# solo-fp1020.net
KiCad netlist of a schematic drawn in EAGLE
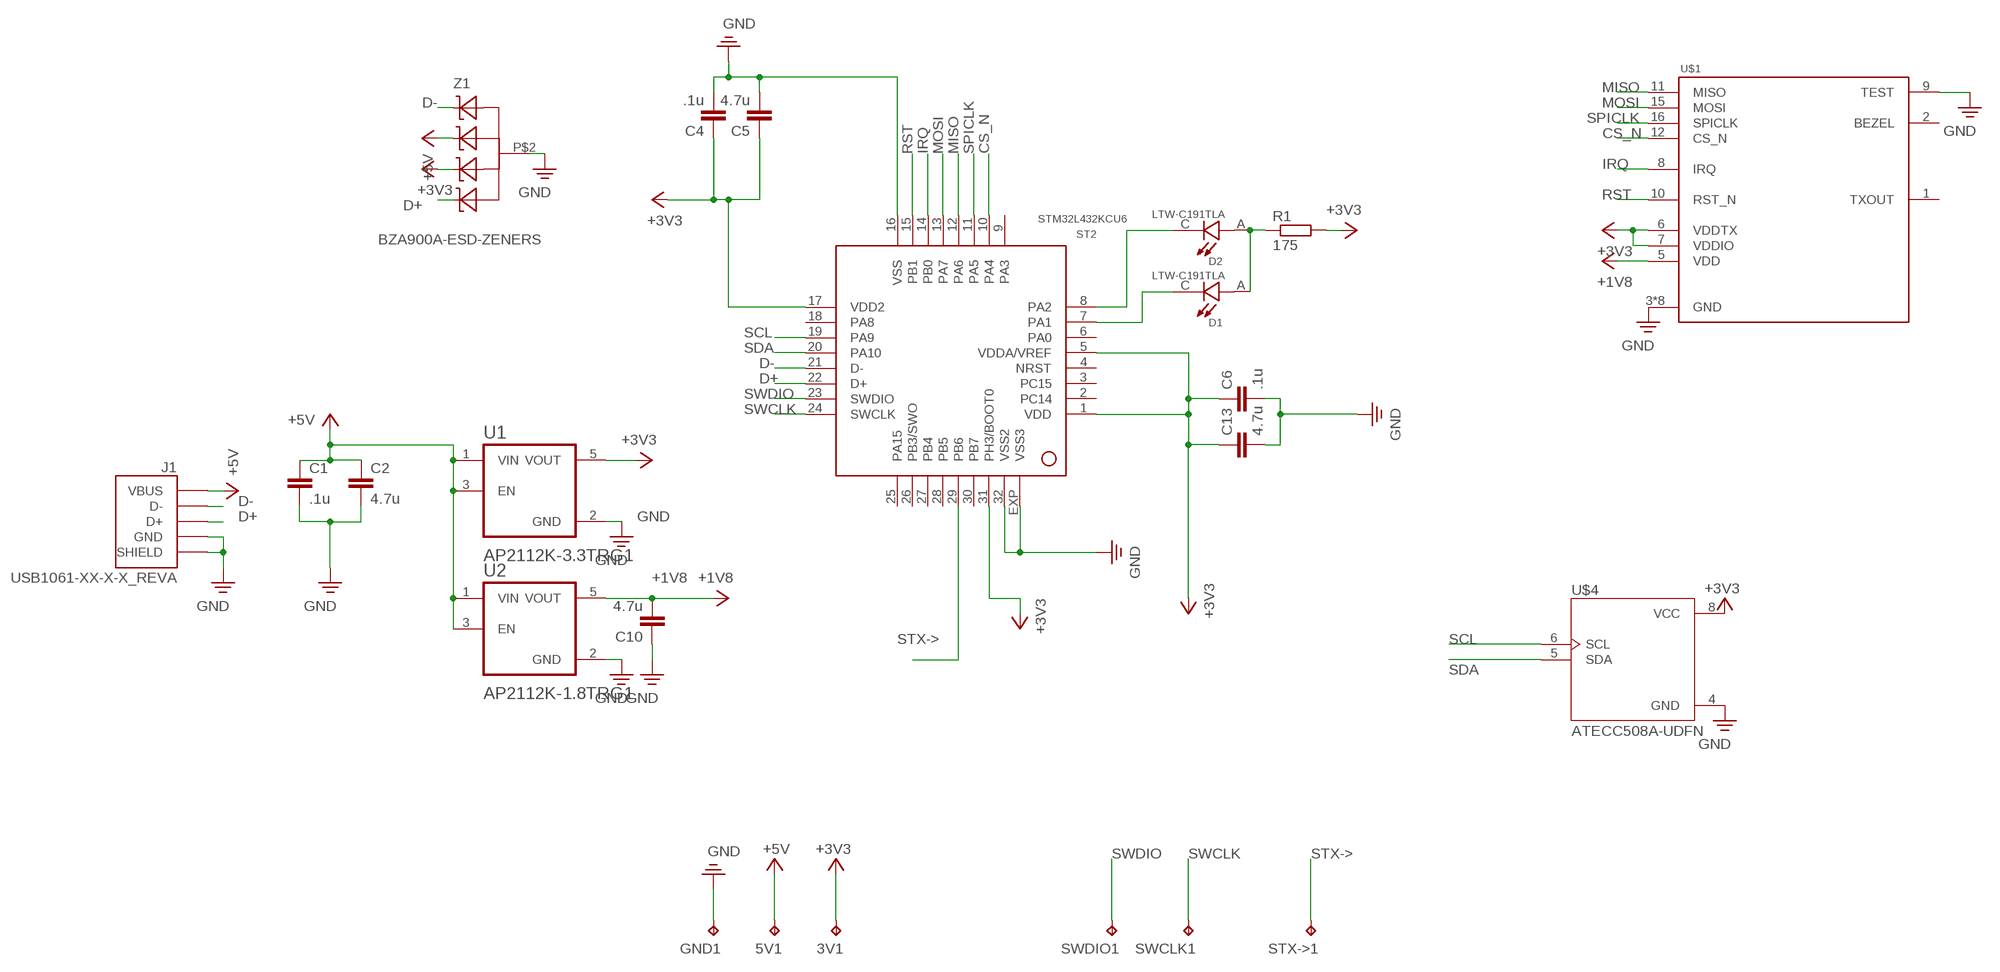
[diagram p0: schematic, sheet 1]

(export (version "E")
  (design (tool "Eeschema 10.0.6"))
  (components
    (comp (ref "3V1")
      (value "TEST_POINT")
      (footprint "eagle-import:B1,27")
      (libsource (lib "eagle-import") (part "TEST_POINT"))
    )
    (comp (ref "5V1")
      (value "TEST_POINT")
      (footprint "eagle-import:B1,27")
      (libsource (lib "eagle-import") (part "TEST_POINT"))
    )
    (comp (ref "C1")
      (value ".1u")
      (footprint "eagle-import:C0603")
      (libsource (lib "eagle-import") (part "C-EUC0603"))
    )
    (comp (ref "C2")
      (value "4.7u")
      (footprint "eagle-import:C0603")
      (libsource (lib "eagle-import") (part "C-EUC0603"))
    )
    (comp (ref "C4")
      (value ".1u")
      (footprint "eagle-import:C0603")
      (libsource (lib "eagle-import") (part "C-EUC0603"))
    )
    (comp (ref "C5")
      (value "4.7u")
      (footprint "eagle-import:C0603")
      (libsource (lib "eagle-import") (part "C-EUC0603"))
    )
    (comp (ref "C6")
      (value ".1u")
      (footprint "eagle-import:C0603")
      (libsource (lib "eagle-import") (part "C-EUC0603"))
    )
    (comp (ref "C10")
      (value "4.7u")
      (footprint "eagle-import:C0603")
      (libsource (lib "eagle-import") (part "C-EUC0603"))
    )
    (comp (ref "C13")
      (value "4.7u")
      (footprint "eagle-import:C0603")
      (libsource (lib "eagle-import") (part "C-EUC0603"))
    )
    (comp (ref "D1")
      (value "LTW-C191TLA")
      (footprint "eagle-import:LEDC1608X65N")
      (fields (field (name "MF") "Lite-On"))
      (libsource (lib "eagle-import") (part "LTW-C191TLA"))
    )
    (comp (ref "D2")
      (value "LTW-C191TLA")
      (footprint "eagle-import:LEDC1608X65N")
      (fields (field (name "MF") "Lite-On"))
      (libsource (lib "eagle-import") (part "LTW-C191TLA"))
    )
    (comp (ref "GND1")
      (value "TEST_POINT")
      (footprint "eagle-import:B1,27")
      (libsource (lib "eagle-import") (part "TEST_POINT"))
    )
    (comp (ref "J1")
      (value "USB1061-XX-X-X_REVA")
      (footprint "eagle-import:GCT_USB1061-XX-X-X_REVA")
      (fields (field (name "MF") "Global Connector Technology") (field (name "MP") "USB1061-GF-L-A"))
      (libsource (lib "eagle-import") (part "USB1061-XX-X-X_REVA"))
    )
    (comp (ref "R1")
      (value "175")
      (footprint "eagle-import:R0603")
      (libsource (lib "eagle-import") (part "R-EU_R0603"))
    )
    (comp (ref "ST2")
      (value "STM32L432KCU6")
      (footprint "eagle-import:QFN32")
      (libsource (lib "eagle-import") (part "STM32L432KCU6"))
    )
    (comp (ref "STX->1")
      (value "TEST_POINT")
      (footprint "eagle-import:B1,27")
      (libsource (lib "eagle-import") (part "TEST_POINT"))
    )
    (comp (ref "SWCLK1")
      (value "TEST_POINT")
      (footprint "eagle-import:B1,27")
      (libsource (lib "eagle-import") (part "TEST_POINT"))
    )
    (comp (ref "SWDIO1")
      (value "TEST_POINT")
      (footprint "eagle-import:B1,27")
      (libsource (lib "eagle-import") (part "TEST_POINT"))
    )
    (comp (ref "U$1")
      (value "FPC1020AM")
      (footprint "eagle-import:FPC1020AM")
      (libsource (lib "eagle-import") (part "FPC1020AM"))
    )
    (comp (ref "U$4")
      (value "ATECC508A-UDFN")
      (footprint "eagle-import:SON50P200X300X60-9N")
      (libsource (lib "eagle-import") (part "ATECC508A-UDFN"))
    )
    (comp (ref "U1")
      (value "AP2112K-3.3TRG1")
      (footprint "eagle-import:SOT95P285X140-5N")
      (fields (field (name "MF") "Diodes Inc."))
      (libsource (lib "eagle-import") (part "AP2112K-3.3TRG1"))
    )
    (comp (ref "U2")
      (value "AP2112K-1.8TRG1")
      (footprint "eagle-import:SOT95P285X140-5N")
      (fields (field (name "MF") "Diodes Inc.") (field (name "MP") "AP2112K-3.3TRG1"))
      (libsource (lib "eagle-import") (part "AP2112K-3.3TRG1"))
    )
    (comp (ref "Z1")
      (value "BZA900A-ESD-ZENERS")
      (footprint "eagle-import:BZA900A")
      (libsource (lib "eagle-import") (part "BZA900A-ESD-ZENERS"))
    )
  )
  (nets
    (net (code "1") (name "+1V8") (class "Default")
      (node (ref "C10") (pin "2") (pinfunction "2_2") (pintype "passive"))
      (node (ref "U$1") (pin "5") (pinfunction "VDD_5") (pintype "power_in"))
      (node (ref "U2") (pin "5") (pinfunction "VOUT_5") (pintype "power_in"))
    )
    (net (code "2") (name "+3V3") (class "Default")
      (node (ref "3V1") (pin "TP") (pinfunction "TP_TP") (pintype "input"))
      (node (ref "C13") (pin "1") (pinfunction "1_1") (pintype "passive"))
      (node (ref "C4") (pin "1") (pinfunction "1_1") (pintype "passive"))
      (node (ref "C5") (pin "1") (pinfunction "1_1") (pintype "passive"))
      (node (ref "C6") (pin "1") (pinfunction "1_1") (pintype "passive"))
      (node (ref "R1") (pin "2") (pinfunction "2_2") (pintype "passive"))
      (node (ref "ST2") (pin "1") (pinfunction "VDD_1") (pintype "bidirectional"))
      (node (ref "ST2") (pin "17") (pinfunction "VDD2_17") (pintype "bidirectional"))
      (node (ref "ST2") (pin "31") (pinfunction "PH3/BOOT0_31") (pintype "bidirectional"))
      (node (ref "ST2") (pin "5") (pinfunction "VDDA/VREF_5") (pintype "bidirectional"))
      (node (ref "U$1") (pin "6") (pinfunction "VDDTX_6") (pintype "power_in"))
      (node (ref "U$1") (pin "7") (pinfunction "VDDIO_7") (pintype "power_in"))
      (node (ref "U$4") (pin "8") (pinfunction "VCC_8") (pintype "power_in"))
      (node (ref "U1") (pin "5") (pinfunction "VOUT_5") (pintype "power_in"))
      (node (ref "Z1") (pin "P$5") (pinfunction "C1_P$5") (pintype "passive"))
    )
    (net (code "3") (name "+5V") (class "Default")
      (node (ref "5V1") (pin "TP") (pinfunction "TP_TP") (pintype "input"))
      (node (ref "C1") (pin "1") (pinfunction "1_1") (pintype "passive"))
      (node (ref "C2") (pin "1") (pinfunction "1_1") (pintype "passive"))
      (node (ref "J1") (pin "1") (pinfunction "VBUS_1") (pintype "power_in"))
      (node (ref "U1") (pin "1") (pinfunction "VIN_1") (pintype "power_in"))
      (node (ref "U1") (pin "3") (pinfunction "EN_3") (pintype "input"))
      (node (ref "U2") (pin "1") (pinfunction "VIN_1") (pintype "power_in"))
      (node (ref "U2") (pin "3") (pinfunction "EN_3") (pintype "input"))
      (node (ref "Z1") (pin "P$1") (pinfunction "C_P$1") (pintype "passive"))
    )
    (net (code "4") (name "/CS_N") (class "Default")
      (node (ref "ST2") (pin "10") (pinfunction "PA4_10") (pintype "bidirectional"))
      (node (ref "U$1") (pin "12") (pinfunction "CS_N_12") (pintype "input"))
    )
    (net (code "5") (name "/D+") (class "Default")
      (node (ref "J1") (pin "3") (pinfunction "D+_3") (pintype "bidirectional"))
      (node (ref "ST2") (pin "22") (pinfunction "D+_22") (pintype "bidirectional"))
      (node (ref "Z1") (pin "P$3") (pinfunction "C3_P$3") (pintype "passive"))
    )
    (net (code "6") (name "/D-") (class "Default")
      (node (ref "J1") (pin "2") (pinfunction "D-_2") (pintype "bidirectional"))
      (node (ref "ST2") (pin "21") (pinfunction "D-_21") (pintype "bidirectional"))
      (node (ref "Z1") (pin "P$4") (pinfunction "C2_P$4") (pintype "passive"))
    )
    (net (code "7") (name "/IRQ") (class "Default")
      (node (ref "ST2") (pin "14") (pinfunction "PB0_14") (pintype "bidirectional"))
      (node (ref "U$1") (pin "8") (pinfunction "IRQ_8") (pintype "output"))
    )
    (net (code "8") (name "/MISO") (class "Default")
      (node (ref "ST2") (pin "12") (pinfunction "PA6_12") (pintype "bidirectional"))
      (node (ref "U$1") (pin "11") (pinfunction "MISO_11") (pintype "bidirectional"))
    )
    (net (code "9") (name "/MOSI") (class "Default")
      (node (ref "ST2") (pin "13") (pinfunction "PA7_13") (pintype "bidirectional"))
      (node (ref "U$1") (pin "15") (pinfunction "MOSI_15") (pintype "bidirectional"))
    )
    (net (code "10") (name "/RST") (class "Default")
      (node (ref "ST2") (pin "15") (pinfunction "PB1_15") (pintype "bidirectional"))
      (node (ref "U$1") (pin "10") (pinfunction "RST_N_10") (pintype "input"))
    )
    (net (code "11") (name "/SCL") (class "Default")
      (node (ref "ST2") (pin "19") (pinfunction "PA9_19") (pintype "bidirectional"))
      (node (ref "U$4") (pin "6") (pinfunction "SCL_6") (pintype "input"))
    )
    (net (code "12") (name "/SDA") (class "Default")
      (node (ref "ST2") (pin "20") (pinfunction "PA10_20") (pintype "bidirectional"))
      (node (ref "U$4") (pin "5") (pinfunction "SDA_5") (pintype "bidirectional"))
    )
    (net (code "13") (name "/SPICLK") (class "Default")
      (node (ref "ST2") (pin "11") (pinfunction "PA5_11") (pintype "bidirectional"))
      (node (ref "U$1") (pin "16") (pinfunction "SPICLK_16") (pintype "input"))
    )
    (net (code "14") (name "/STX->") (class "Default")
      (node (ref "ST2") (pin "29") (pinfunction "PB6_29") (pintype "bidirectional"))
      (node (ref "STX->1") (pin "TP") (pinfunction "TP_TP") (pintype "input"))
    )
    (net (code "15") (name "/SWCLK") (class "Default")
      (node (ref "ST2") (pin "24") (pinfunction "SWCLK_24") (pintype "bidirectional"))
      (node (ref "SWCLK1") (pin "TP") (pinfunction "TP_TP") (pintype "input"))
    )
    (net (code "16") (name "/SWDIO") (class "Default")
      (node (ref "ST2") (pin "23") (pinfunction "SWDIO_23") (pintype "bidirectional"))
      (node (ref "SWDIO1") (pin "TP") (pinfunction "TP_TP") (pintype "input"))
    )
    (net (code "17") (name "GND") (class "Default")
      (node (ref "C1") (pin "2") (pinfunction "2_2") (pintype "passive"))
      (node (ref "C10") (pin "1") (pinfunction "1_1") (pintype "passive"))
      (node (ref "C13") (pin "2") (pinfunction "2_2") (pintype "passive"))
      (node (ref "C2") (pin "2") (pinfunction "2_2") (pintype "passive"))
      (node (ref "C4") (pin "2") (pinfunction "2_2") (pintype "passive"))
      (node (ref "C5") (pin "2") (pinfunction "2_2") (pintype "passive"))
      (node (ref "C6") (pin "2") (pinfunction "2_2") (pintype "passive"))
      (node (ref "GND1") (pin "TP") (pinfunction "TP_TP") (pintype "input"))
      (node (ref "J1") (pin "4") (pinfunction "GND_4") (pintype "power_in"))
      (node (ref "J1") (pin "5") (pinfunction "SHIELD_5") (pintype "power_in"))
      (node (ref "J1") (pin "6") (pinfunction "SHIELD_6") (pintype "power_in"))
      (node (ref "ST2") (pin "16") (pinfunction "VSS_16") (pintype "bidirectional"))
      (node (ref "ST2") (pin "32") (pinfunction "VSS2_32") (pintype "bidirectional"))
      (node (ref "ST2") (pin "EXP") (pinfunction "VSS3_EXP") (pintype "bidirectional"))
      (node (ref "U$1") (pin "13") (pinfunction "GND_13") (pintype "power_in"))
      (node (ref "U$1") (pin "14") (pinfunction "GND_14") (pintype "power_in"))
      (node (ref "U$1") (pin "17") (pinfunction "GND_17") (pintype "power_in"))
      (node (ref "U$1") (pin "18") (pinfunction "GND_18") (pintype "power_in"))
      (node (ref "U$1") (pin "19") (pinfunction "GND_19") (pintype "power_in"))
      (node (ref "U$1") (pin "20") (pinfunction "GND_20") (pintype "power_in"))
      (node (ref "U$1") (pin "3") (pinfunction "GND_3") (pintype "power_in"))
      (node (ref "U$1") (pin "4") (pinfunction "GND_4") (pintype "power_in"))
      (node (ref "U$1") (pin "9") (pinfunction "TEST_9") (pintype "bidirectional"))
      (node (ref "U$4") (pin "4") (pinfunction "GND_4") (pintype "power_in"))
      (node (ref "U1") (pin "2") (pinfunction "GND_2") (pintype "power_in"))
      (node (ref "U2") (pin "2") (pinfunction "GND_2") (pintype "power_in"))
      (node (ref "Z1") (pin "P$2") (pinfunction "P$1_P$2") (pintype "bidirectional"))
    )
    (net (code "18") (name "Net-(D1-PadA)") (class "Default")
      (node (ref "D1") (pin "A") (pinfunction "A_A") (pintype "passive"))
      (node (ref "D2") (pin "A") (pinfunction "A_A") (pintype "passive"))
      (node (ref "R1") (pin "1") (pinfunction "1_1") (pintype "passive"))
    )
    (net (code "19") (name "Net-(ST2-PA1)") (class "Default")
      (node (ref "D1") (pin "C") (pinfunction "C_C") (pintype "passive"))
      (node (ref "ST2") (pin "7") (pinfunction "PA1_7") (pintype "bidirectional"))
    )
    (net (code "20") (name "Net-(ST2-PA2)") (class "Default")
      (node (ref "D2") (pin "C") (pinfunction "C_C") (pintype "passive"))
      (node (ref "ST2") (pin "8") (pinfunction "PA2_8") (pintype "bidirectional"))
    )
    (net (code "21") (name "unconnected-(ST2-NRST-Pad4)") (class "Default")
      (node (ref "ST2") (pin "4") (pinfunction "NRST_4") (pintype "bidirectional"))
    )
    (net (code "22") (name "unconnected-(ST2-PA0-Pad6)") (class "Default")
      (node (ref "ST2") (pin "6") (pinfunction "PA0_6") (pintype "bidirectional"))
    )
    (net (code "23") (name "unconnected-(ST2-PA3-Pad9)") (class "Default")
      (node (ref "ST2") (pin "9") (pinfunction "PA3_9") (pintype "bidirectional"))
    )
    (net (code "24") (name "unconnected-(ST2-PA8-Pad18)") (class "Default")
      (node (ref "ST2") (pin "18") (pinfunction "PA8_18") (pintype "bidirectional"))
    )
    (net (code "25") (name "unconnected-(ST2-PA15-Pad25)") (class "Default")
      (node (ref "ST2") (pin "25") (pinfunction "PA15_25") (pintype "bidirectional"))
    )
    (net (code "26") (name "unconnected-(ST2-PB3{slash}SWO-Pad26)") (class "Default")
      (node (ref "ST2") (pin "26") (pinfunction "PB3/SWO_26") (pintype "bidirectional"))
    )
    (net (code "27") (name "unconnected-(ST2-PB4-Pad27)") (class "Default")
      (node (ref "ST2") (pin "27") (pinfunction "PB4_27") (pintype "bidirectional"))
    )
    (net (code "28") (name "unconnected-(ST2-PB5-Pad28)") (class "Default")
      (node (ref "ST2") (pin "28") (pinfunction "PB5_28") (pintype "bidirectional"))
    )
    (net (code "29") (name "unconnected-(ST2-PB7-Pad30)") (class "Default")
      (node (ref "ST2") (pin "30") (pinfunction "PB7_30") (pintype "bidirectional"))
    )
    (net (code "30") (name "unconnected-(ST2-PC14-Pad2)") (class "Default")
      (node (ref "ST2") (pin "2") (pinfunction "PC14_2") (pintype "bidirectional"))
    )
    (net (code "31") (name "unconnected-(ST2-PC15-Pad3)") (class "Default")
      (node (ref "ST2") (pin "3") (pinfunction "PC15_3") (pintype "bidirectional"))
    )
    (net (code "32") (name "unconnected-(U$1-BEZEL-Pad2)") (class "Default")
      (node (ref "U$1") (pin "2") (pinfunction "BEZEL_2") (pintype "bidirectional"))
    )
    (net (code "33") (name "unconnected-(U$1-TXOUT-Pad1)") (class "Default")
      (node (ref "U$1") (pin "1") (pinfunction "TXOUT_1") (pintype "output"))
    )
  )
)
